# illuminator_control_boardv1-4.net
KiCad netlist of a schematic drawn in EAGLE
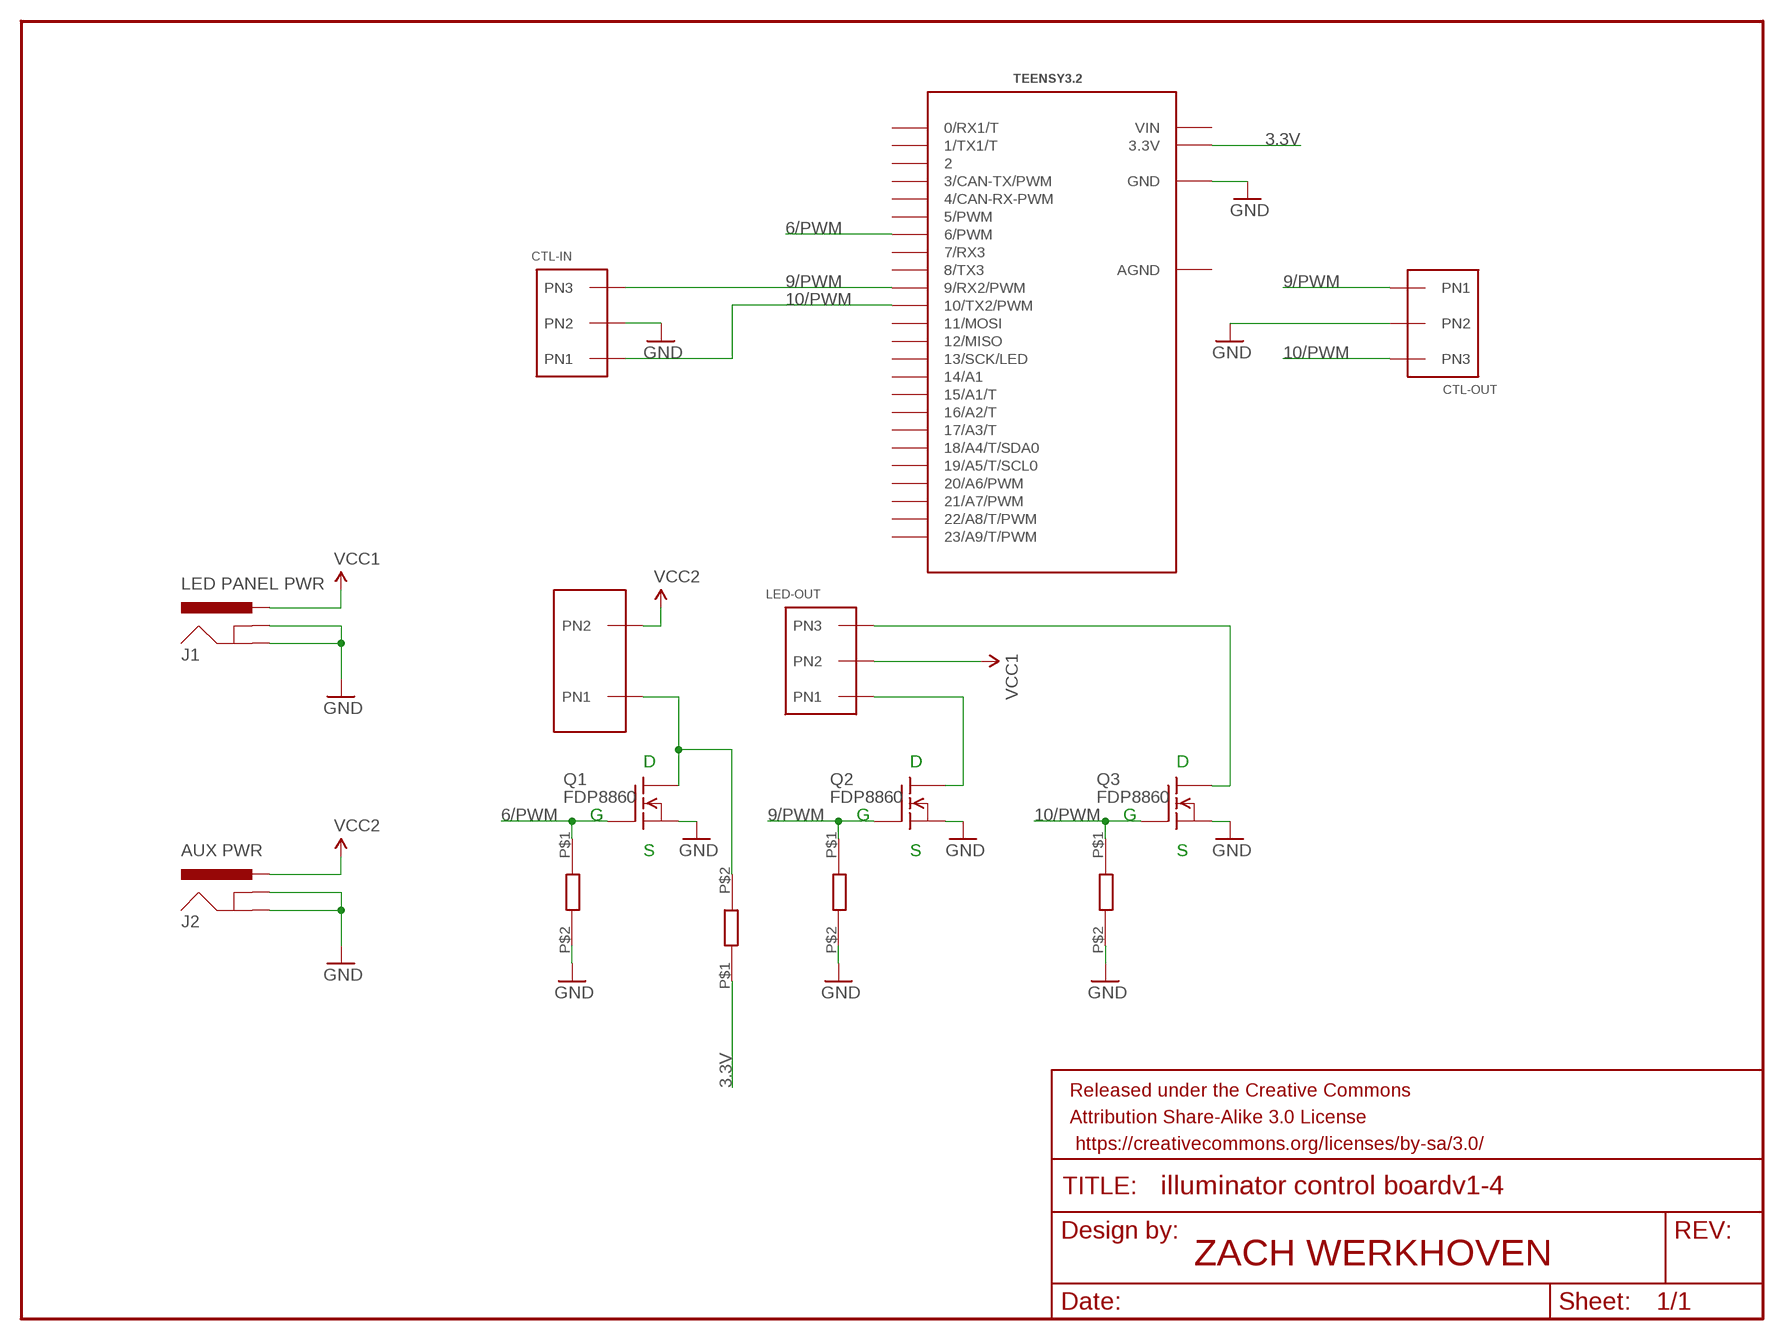
[diagram p0: schematic, sheet 1]

(export (version "E")
  (design (tool "Eeschema 10.0.6"))
  (components
    (comp (ref "AUX-OUT")
      (value "AUX-OUT")
      (footprint "eagle-import:MLX-2PN")
      (libsource (lib "eagle-import") (part "MLX-2PN"))
    )
    (comp (ref "CTL-IN")
      (value "MLX-3PN")
      (footprint "eagle-import:MLX-3PN")
      (libsource (lib "eagle-import") (part "MLX-3PN"))
    )
    (comp (ref "CTL-OUT")
      (value "MLX-3PN")
      (footprint "eagle-import:MLX-3PN")
      (libsource (lib "eagle-import") (part "MLX-3PN"))
    )
    (comp (ref "FRAME1")
      (value "FRAME-LETTER")
      (footprint "eagle-import:CREATIVE_COMMONS")
      (libsource (lib "eagle-import") (part "FRAME-LETTER"))
    )
    (comp (ref "J1")
      (value "LED PANEL PWR")
      (footprint "eagle-import:POWER_JACK_PTH_BREAD")
      (libsource (lib "eagle-import") (part "POWER_JACKPTH_BREAD"))
    )
    (comp (ref "J2")
      (value "AUX PWR")
      (footprint "eagle-import:POWER_JACK_PTH_BREAD")
      (libsource (lib "eagle-import") (part "POWER_JACKPTH_BREAD"))
    )
    (comp (ref "LED-OUT")
      (value "MLX-3PN")
      (footprint "eagle-import:MLX-3PN")
      (libsource (lib "eagle-import") (part "MLX-3PN"))
    )
    (comp (ref "Q1")
      (value "FDP8860")
      (footprint "eagle-import:TO220")
      (libsource (lib "eagle-import") (part "BUZ10"))
    )
    (comp (ref "Q2")
      (value "FDP8860")
      (footprint "eagle-import:TO220")
      (libsource (lib "eagle-import") (part "transistor-fet_BUZ10"))
    )
    (comp (ref "Q3")
      (value "FDP8860")
      (footprint "eagle-import:TO220")
      (libsource (lib "eagle-import") (part "transistor-fet_BUZ10"))
    )
    (comp (ref "TEENSY3.2")
      (value "TEENSY_3.1_DIL")
      (footprint "eagle-import:TEENSY3-DIL")
      (libsource (lib "eagle-import") (part "TEENSY_3.1_DIL"))
    )
    (comp (ref "U$1")
      (value "SMD-1206")
      (footprint "eagle-import:SMD-1206")
      (libsource (lib "eagle-import") (part "SMD-1206"))
    )
    (comp (ref "U$2")
      (value "SMD-1206")
      (footprint "eagle-import:SMD-1206")
      (libsource (lib "eagle-import") (part "SMD-1206"))
    )
    (comp (ref "U$3")
      (value "SMD-1206")
      (footprint "eagle-import:SMD-1206")
      (libsource (lib "eagle-import") (part "SMD-1206"))
    )
    (comp (ref "U$5")
      (value "SMD-1206")
      (footprint "eagle-import:SMD-1206")
      (libsource (lib "eagle-import") (part "SMD-1206"))
    )
  )
  (nets
    (net (code "1") (name "/3.3V") (class "Default")
      (node (ref "TEENSY3.2") (pin "3.3V") (pinfunction "3.3V_3.3V") (pintype "power_in"))
      (node (ref "U$5") (pin "P$1") (pinfunction "P$1_P$1") (pintype "bidirectional"))
    )
    (net (code "2") (name "/6{slash}PWM") (class "Default")
      (node (ref "Q1") (pin "1") (pinfunction "G_1") (pintype "passive"))
      (node (ref "TEENSY3.2") (pin "6") (pinfunction "6/PWM_6") (pintype "bidirectional"))
      (node (ref "U$1") (pin "P$1") (pinfunction "P$1_P$1") (pintype "bidirectional"))
    )
    (net (code "3") (name "/9{slash}PWM") (class "Default")
      (node (ref "CTL-IN") (pin "PN3") (pinfunction "PN3_PN3") (pintype "bidirectional"))
      (node (ref "CTL-OUT") (pin "PN1") (pinfunction "PN1_PN1") (pintype "bidirectional"))
      (node (ref "Q2") (pin "1") (pinfunction "G_1") (pintype "passive"))
      (node (ref "TEENSY3.2") (pin "9") (pinfunction "9/RX2/PWM_9") (pintype "bidirectional"))
      (node (ref "U$2") (pin "P$1") (pinfunction "P$1_P$1") (pintype "bidirectional"))
    )
    (net (code "4") (name "/10{slash}PWM") (class "Default")
      (node (ref "CTL-IN") (pin "PN1") (pinfunction "PN1_PN1") (pintype "bidirectional"))
      (node (ref "CTL-OUT") (pin "PN3") (pinfunction "PN3_PN3") (pintype "bidirectional"))
      (node (ref "Q3") (pin "1") (pinfunction "G_1") (pintype "passive"))
      (node (ref "TEENSY3.2") (pin "10") (pinfunction "10/TX2/PWM_10") (pintype "bidirectional"))
      (node (ref "U$3") (pin "P$1") (pinfunction "P$1_P$1") (pintype "bidirectional"))
    )
    (net (code "5") (name "/AGND") (class "Default")
      (node (ref "TEENSY3.2") (pin "AGND") (pinfunction "AGND_AGND") (pintype "power_in"))
    )
    (net (code "6") (name "/VIN") (class "Default")
      (node (ref "TEENSY3.2") (pin "VIN") (pinfunction "VIN_VIN") (pintype "power_in"))
    )
    (net (code "7") (name "GND") (class "Default")
      (node (ref "CTL-IN") (pin "PN2") (pinfunction "PN2_PN2") (pintype "bidirectional"))
      (node (ref "CTL-OUT") (pin "PN2") (pinfunction "PN2_PN2") (pintype "bidirectional"))
      (node (ref "J1") (pin "GND") (pinfunction "GND_GND") (pintype "bidirectional"))
      (node (ref "J1") (pin "GNDBREAK") (pinfunction "GNDBREAK_GNDBREAK") (pintype "bidirectional"))
      (node (ref "J2") (pin "GND") (pinfunction "GND_GND") (pintype "bidirectional"))
      (node (ref "J2") (pin "GNDBREAK") (pinfunction "GNDBREAK_GNDBREAK") (pintype "bidirectional"))
      (node (ref "Q1") (pin "3") (pinfunction "S_3") (pintype "passive"))
      (node (ref "Q2") (pin "3") (pinfunction "S_3") (pintype "passive"))
      (node (ref "Q3") (pin "3") (pinfunction "S_3") (pintype "passive"))
      (node (ref "TEENSY3.2") (pin "GND") (pinfunction "GND_GND") (pintype "power_in"))
      (node (ref "U$1") (pin "P$2") (pinfunction "P$2_P$2") (pintype "bidirectional"))
      (node (ref "U$2") (pin "P$2") (pinfunction "P$2_P$2") (pintype "bidirectional"))
      (node (ref "U$3") (pin "P$2") (pinfunction "P$2_P$2") (pintype "bidirectional"))
    )
    (net (code "8") (name "Net-(AUX-OUT-PN1)") (class "Default")
      (node (ref "AUX-OUT") (pin "PD1") (pinfunction "PN1_PD1") (pintype "bidirectional"))
      (node (ref "Q1") (pin "2") (pinfunction "D_2") (pintype "passive"))
      (node (ref "U$5") (pin "P$2") (pinfunction "P$2_P$2") (pintype "bidirectional"))
    )
    (net (code "9") (name "Net-(Q2-D)") (class "Default")
      (node (ref "LED-OUT") (pin "PN1") (pinfunction "PN1_PN1") (pintype "bidirectional"))
      (node (ref "Q2") (pin "2") (pinfunction "D_2") (pintype "passive"))
    )
    (net (code "10") (name "Net-(Q3-D)") (class "Default")
      (node (ref "LED-OUT") (pin "PN3") (pinfunction "PN3_PN3") (pintype "bidirectional"))
      (node (ref "Q3") (pin "2") (pinfunction "D_2") (pintype "passive"))
    )
    (net (code "11") (name "VCC1") (class "Default")
      (node (ref "AUX-OUT") (pin "PD2") (pinfunction "PN2_PD2") (pintype "bidirectional"))
      (node (ref "J1") (pin "PWR") (pinfunction "PWR_PWR") (pintype "bidirectional"))
      (node (ref "J2") (pin "PWR") (pinfunction "PWR_PWR") (pintype "bidirectional"))
      (node (ref "LED-OUT") (pin "PN2") (pinfunction "PN2_PN2") (pintype "bidirectional"))
    )
    (net (code "12") (name "unconnected-(TEENSY3.2-0{slash}RX1{slash}T-Pad0)") (class "Default")
      (node (ref "TEENSY3.2") (pin "0") (pinfunction "0/RX1/T_0") (pintype "bidirectional"))
    )
    (net (code "13") (name "unconnected-(TEENSY3.2-1{slash}TX1{slash}T-Pad1)") (class "Default")
      (node (ref "TEENSY3.2") (pin "1") (pinfunction "1/TX1/T_1") (pintype "bidirectional"))
    )
    (net (code "14") (name "unconnected-(TEENSY3.2-3{slash}CAN-TX{slash}PWM-Pad3)") (class "Default")
      (node (ref "TEENSY3.2") (pin "3") (pinfunction "3/CAN-TX/PWM_3") (pintype "bidirectional"))
    )
    (net (code "15") (name "unconnected-(TEENSY3.2-4{slash}CAN-RX-PWM-Pad4)") (class "Default")
      (node (ref "TEENSY3.2") (pin "4") (pinfunction "4/CAN-RX-PWM_4") (pintype "bidirectional"))
    )
    (net (code "16") (name "unconnected-(TEENSY3.2-5{slash}PWM-Pad5)") (class "Default")
      (node (ref "TEENSY3.2") (pin "5") (pinfunction "5/PWM_5") (pintype "bidirectional"))
    )
    (net (code "17") (name "unconnected-(TEENSY3.2-7{slash}RX3-Pad7)") (class "Default")
      (node (ref "TEENSY3.2") (pin "7") (pinfunction "7/RX3_7") (pintype "bidirectional"))
    )
    (net (code "18") (name "unconnected-(TEENSY3.2-8{slash}TX3-Pad8)") (class "Default")
      (node (ref "TEENSY3.2") (pin "8") (pinfunction "8/TX3_8") (pintype "bidirectional"))
    )
    (net (code "19") (name "unconnected-(TEENSY3.2-11{slash}MOSI-Pad11)") (class "Default")
      (node (ref "TEENSY3.2") (pin "11") (pinfunction "11/MOSI_11") (pintype "bidirectional"))
    )
    (net (code "20") (name "unconnected-(TEENSY3.2-12{slash}MISO-Pad12)") (class "Default")
      (node (ref "TEENSY3.2") (pin "12") (pinfunction "12/MISO_12") (pintype "bidirectional"))
    )
    (net (code "21") (name "unconnected-(TEENSY3.2-13{slash}SCK{slash}LED-Pad13)") (class "Default")
      (node (ref "TEENSY3.2") (pin "13") (pinfunction "13/SCK/LED_13") (pintype "bidirectional"))
    )
    (net (code "22") (name "unconnected-(TEENSY3.2-14{slash}A1-Pad14{slash}A0)") (class "Default")
      (node (ref "TEENSY3.2") (pin "14/A0") (pinfunction "14/A1_14/A0") (pintype "bidirectional"))
    )
    (net (code "23") (name "unconnected-(TEENSY3.2-15{slash}A1{slash}T-Pad15{slash}A1)") (class "Default")
      (node (ref "TEENSY3.2") (pin "15/A1") (pinfunction "15/A1/T_15/A1") (pintype "bidirectional"))
    )
    (net (code "24") (name "unconnected-(TEENSY3.2-16{slash}A2{slash}T-Pad16{slash}A2)") (class "Default")
      (node (ref "TEENSY3.2") (pin "16/A2") (pinfunction "16/A2/T_16/A2") (pintype "bidirectional"))
    )
    (net (code "25") (name "unconnected-(TEENSY3.2-17{slash}A3{slash}T-Pad17{slash}A3)") (class "Default")
      (node (ref "TEENSY3.2") (pin "17/A3") (pinfunction "17/A3/T_17/A3") (pintype "bidirectional"))
    )
    (net (code "26") (name "unconnected-(TEENSY3.2-18{slash}A4{slash}T{slash}SDA0-Pad18{slash}A4)") (class "Default")
      (node (ref "TEENSY3.2") (pin "18/A4") (pinfunction "18/A4/T/SDA0_18/A4") (pintype "bidirectional"))
    )
    (net (code "27") (name "unconnected-(TEENSY3.2-19{slash}A5{slash}T{slash}SCL0-Pad19{slash}A5)") (class "Default")
      (node (ref "TEENSY3.2") (pin "19/A5") (pinfunction "19/A5/T/SCL0_19/A5") (pintype "bidirectional"))
    )
    (net (code "28") (name "unconnected-(TEENSY3.2-20{slash}A6{slash}PWM-Pad20{slash}A6)") (class "Default")
      (node (ref "TEENSY3.2") (pin "20/A6") (pinfunction "20/A6/PWM_20/A6") (pintype "bidirectional"))
    )
    (net (code "29") (name "unconnected-(TEENSY3.2-21{slash}A7{slash}PWM-Pad21{slash}A7)") (class "Default")
      (node (ref "TEENSY3.2") (pin "21/A7") (pinfunction "21/A7/PWM_21/A7") (pintype "bidirectional"))
    )
    (net (code "30") (name "unconnected-(TEENSY3.2-22{slash}A8{slash}T{slash}PWM-Pad22{slash}A8)") (class "Default")
      (node (ref "TEENSY3.2") (pin "22/A8") (pinfunction "22/A8/T/PWM_22/A8") (pintype "bidirectional"))
    )
    (net (code "31") (name "unconnected-(TEENSY3.2-23{slash}A9{slash}T{slash}PWM-Pad23{slash}A9)") (class "Default")
      (node (ref "TEENSY3.2") (pin "23/A9") (pinfunction "23/A9/T/PWM_23/A9") (pintype "bidirectional"))
    )
    (net (code "32") (name "unconnected-(TEENSY3.2-Pad2)") (class "Default")
      (node (ref "TEENSY3.2") (pin "2") (pinfunction "2_2") (pintype "bidirectional"))
    )
  )
)
